# SOIC-8_v11.net
KiCad netlist of a schematic drawn in EAGLE
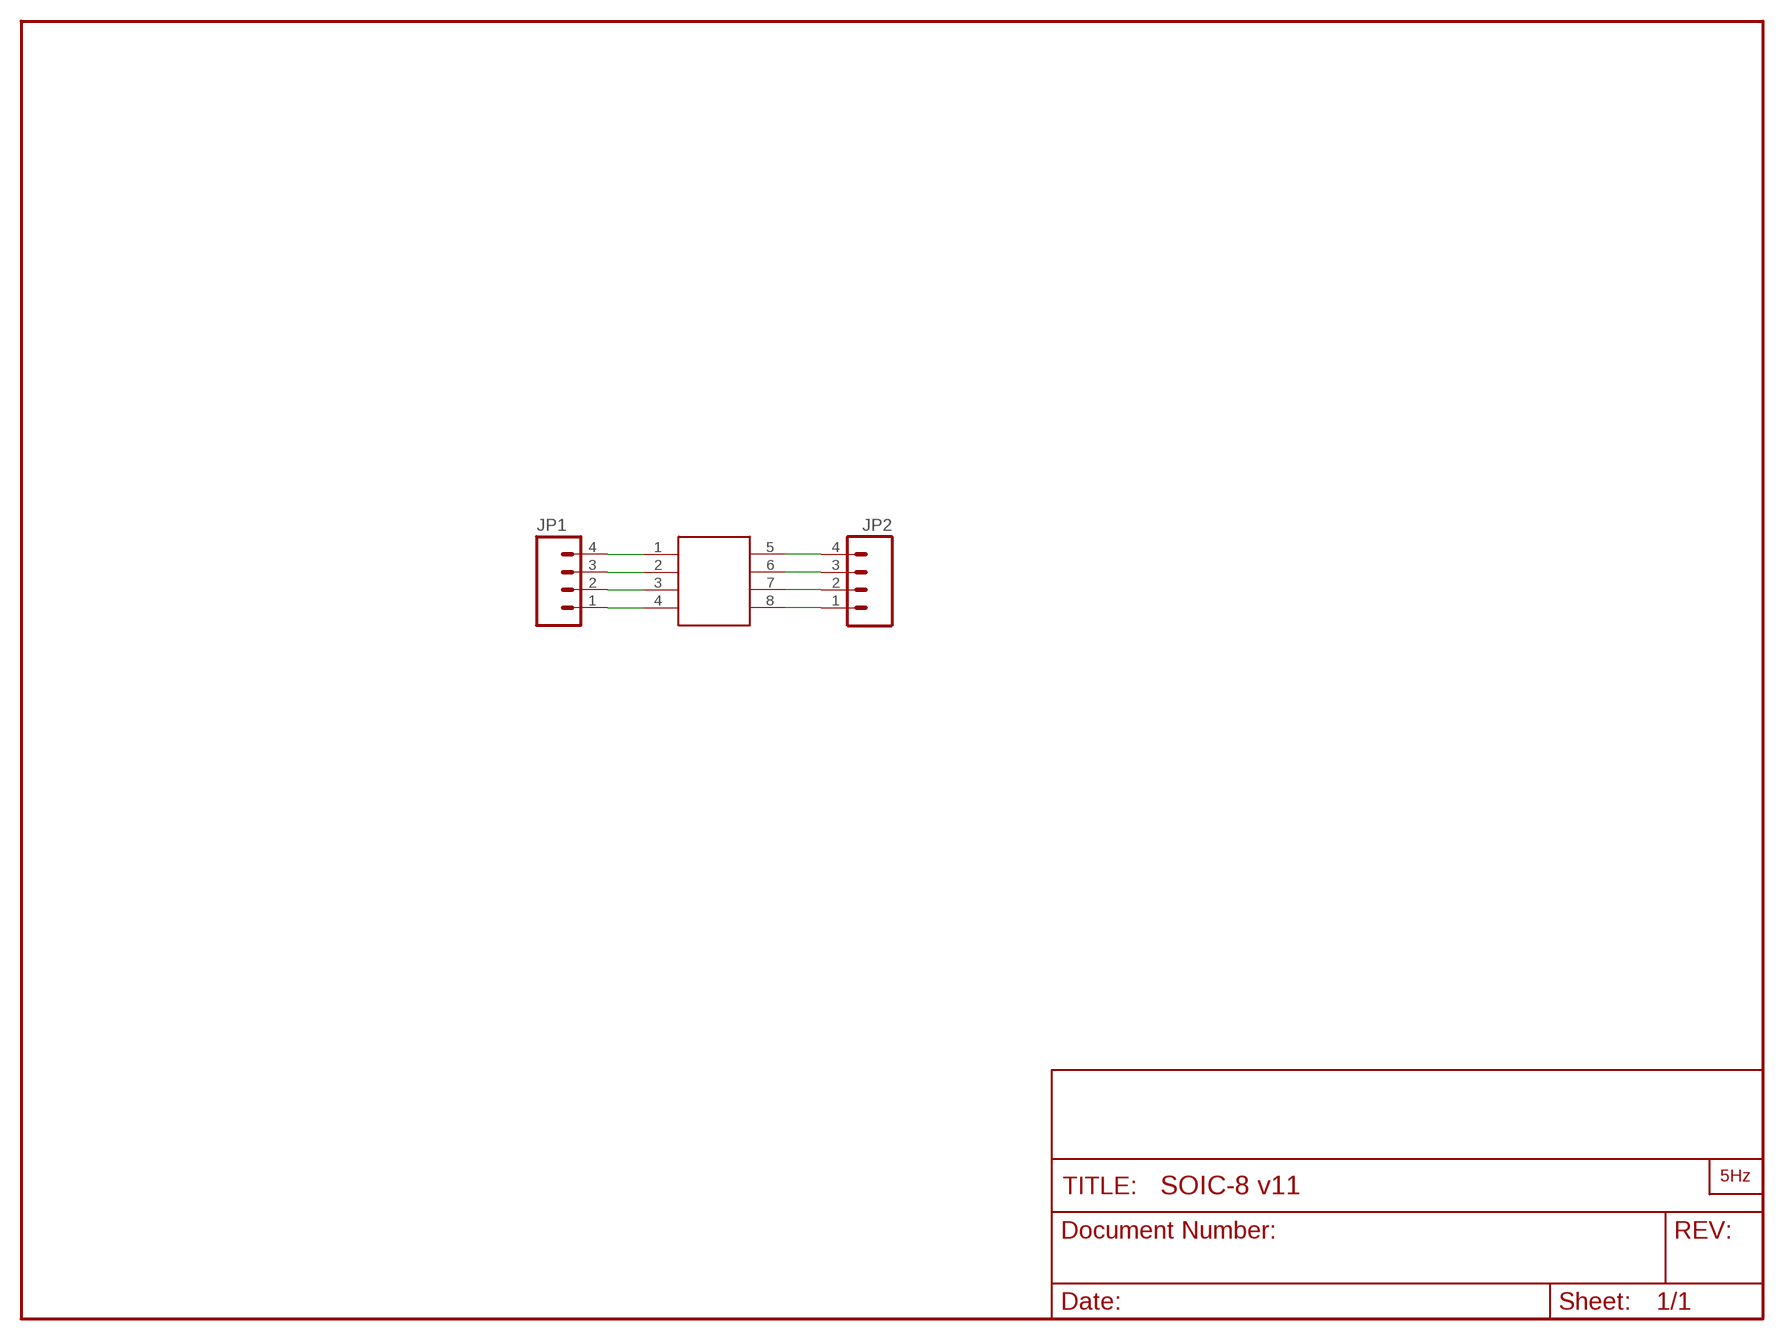
[diagram p0: schematic, sheet 1]

(export (version "E")
  (design (tool "Eeschema 10.0.6"))
  (components
    (comp (ref "JP1")
      (value "M04PTH")
      (footprint "eagle-import:1X04")
      (libsource (lib "eagle-import") (part "M04PTH"))
    )
    (comp (ref "JP2")
      (value "M04PTH")
      (footprint "eagle-import:1X04")
      (libsource (lib "eagle-import") (part "M04PTH"))
    )
    (comp (ref "U$1")
      (value "SOIC8SOIC8")
      (footprint "eagle-import:SOIC8")
      (libsource (lib "eagle-import") (part "SOIC8SOIC8"))
    )
    (comp (ref "U$2")
      (value "LOGO2_SILKC5MM")
      (footprint "eagle-import:CIRCULO2_5MM")
      (libsource (lib "eagle-import") (part "LOGO2_SILKC5MM"))
    )
  )
  (nets
    (net (code "1") (name "Net-(U$1-P$1)") (class "Default")
      (node (ref "JP1") (pin "4") (pinfunction "4_4") (pintype "passive"))
      (node (ref "U$1") (pin "1") (pinfunction "P$1_1") (pintype "bidirectional"))
    )
    (net (code "2") (name "Net-(U$1-P$2)") (class "Default")
      (node (ref "JP1") (pin "3") (pinfunction "3_3") (pintype "passive"))
      (node (ref "U$1") (pin "2") (pinfunction "P$2_2") (pintype "bidirectional"))
    )
    (net (code "3") (name "Net-(U$1-P$3)") (class "Default")
      (node (ref "JP1") (pin "2") (pinfunction "2_2") (pintype "passive"))
      (node (ref "U$1") (pin "3") (pinfunction "P$3_3") (pintype "bidirectional"))
    )
    (net (code "4") (name "Net-(U$1-P$4)") (class "Default")
      (node (ref "JP1") (pin "1") (pinfunction "1_1") (pintype "passive"))
      (node (ref "U$1") (pin "4") (pinfunction "P$4_4") (pintype "bidirectional"))
    )
    (net (code "5") (name "Net-(U$1-P$5)") (class "Default")
      (node (ref "JP2") (pin "4") (pinfunction "4_4") (pintype "passive"))
      (node (ref "U$1") (pin "5") (pinfunction "P$5_5") (pintype "bidirectional"))
    )
    (net (code "6") (name "Net-(U$1-P$6)") (class "Default")
      (node (ref "JP2") (pin "3") (pinfunction "3_3") (pintype "passive"))
      (node (ref "U$1") (pin "6") (pinfunction "P$6_6") (pintype "bidirectional"))
    )
    (net (code "7") (name "Net-(U$1-P$7)") (class "Default")
      (node (ref "JP2") (pin "2") (pinfunction "2_2") (pintype "passive"))
      (node (ref "U$1") (pin "7") (pinfunction "P$7_7") (pintype "bidirectional"))
    )
    (net (code "8") (name "Net-(U$1-P$8)") (class "Default")
      (node (ref "JP2") (pin "1") (pinfunction "1_1") (pintype "passive"))
      (node (ref "U$1") (pin "8") (pinfunction "P$8_8") (pintype "bidirectional"))
    )
  )
)
